# MB-7SEGMENT-74HC595.net
KiCad netlist of a schematic drawn in EAGLE
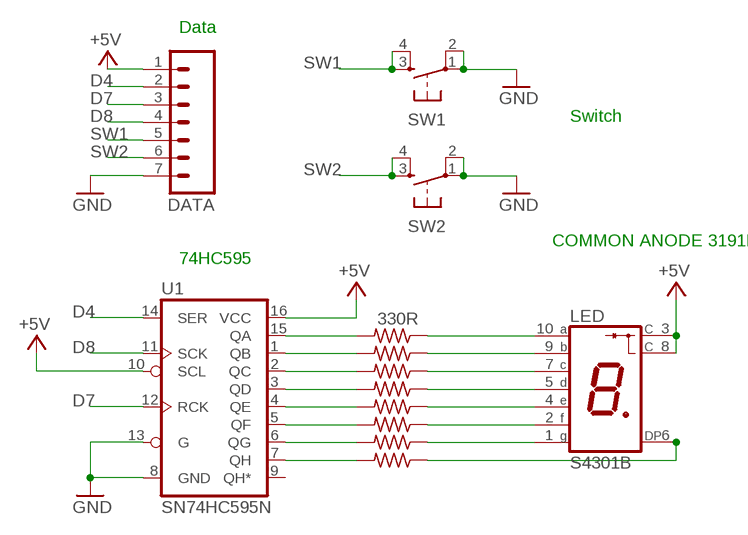
[diagram p0: schematic, sheet 1]

(export (version "E")
  (design (tool "Eeschema 10.0.6"))
  (components
    (comp (ref "DATA")
      (value "M07")
      (footprint "eagle-import:1X07")
      (libsource (lib "eagle-import") (part "M07"))
    )
    (comp (ref "LED")
      (value "S4301B")
      (footprint "eagle-import:S4301B")
      (libsource (lib "eagle-import") (part "S4301B"))
    )
    (comp (ref "R1")
      (value "330R")
      (footprint "eagle-import:0204_5")
      (libsource (lib "eagle-import") (part "R-US_0204/5"))
    )
    (comp (ref "R3")
      (value "330R")
      (footprint "eagle-import:0204_5")
      (libsource (lib "eagle-import") (part "R-US_0204/5"))
    )
    (comp (ref "R4")
      (value "330R")
      (footprint "eagle-import:0204_5")
      (libsource (lib "eagle-import") (part "R-US_0204/5"))
    )
    (comp (ref "R5")
      (value "330R")
      (footprint "eagle-import:0204_5")
      (libsource (lib "eagle-import") (part "R-US_0204/5"))
    )
    (comp (ref "R6")
      (value "330R")
      (footprint "eagle-import:0204_5")
      (libsource (lib "eagle-import") (part "R-US_0204/5"))
    )
    (comp (ref "R7")
      (value "330R")
      (footprint "eagle-import:0204_5")
      (libsource (lib "eagle-import") (part "R-US_0204/5"))
    )
    (comp (ref "R8")
      (value "330R")
      (footprint "eagle-import:0204_5")
      (libsource (lib "eagle-import") (part "R-US_0204/5"))
    )
    (comp (ref "R9")
      (value "330R")
      (footprint "eagle-import:0204_5")
      (libsource (lib "eagle-import") (part "R-US_0204/5"))
    )
    (comp (ref "SW1")
      (value "DTS-6")
      (footprint "eagle-import:DTS-6")
      (libsource (lib "eagle-import") (part "DTS-6"))
    )
    (comp (ref "SW2")
      (value "DTS-6")
      (footprint "eagle-import:DTS-6")
      (libsource (lib "eagle-import") (part "DTS-6"))
    )
    (comp (ref "U1")
      (value "SN74HC595N")
      (footprint "eagle-import:DIP16")
      (libsource (lib "eagle-import") (part "74595NHC"))
    )
  )
  (nets
    (net (code "1") (name "+5V") (class "Default")
      (node (ref "DATA") (pin "1") (pinfunction "1_1") (pintype "passive"))
      (node (ref "LED") (pin "3") (pinfunction "C_3") (pintype "passive"))
      (node (ref "LED") (pin "8") (pinfunction "C_8") (pintype "passive"))
      (node (ref "U1") (pin "10") (pinfunction "SCL_10") (pintype "input"))
      (node (ref "U1") (pin "16") (pinfunction "VCC_16") (pintype "power_in"))
    )
    (net (code "2") (name "/D4") (class "Default")
      (node (ref "DATA") (pin "2") (pinfunction "2_2") (pintype "passive"))
      (node (ref "U1") (pin "14") (pinfunction "SER_14") (pintype "input"))
    )
    (net (code "3") (name "/D7") (class "Default")
      (node (ref "DATA") (pin "3") (pinfunction "3_3") (pintype "passive"))
      (node (ref "U1") (pin "12") (pinfunction "RCK_12") (pintype "input"))
    )
    (net (code "4") (name "/D8") (class "Default")
      (node (ref "DATA") (pin "4") (pinfunction "4_4") (pintype "passive"))
      (node (ref "U1") (pin "11") (pinfunction "SCK_11") (pintype "input"))
    )
    (net (code "5") (name "/SW1") (class "Default")
      (node (ref "DATA") (pin "5") (pinfunction "5_5") (pintype "passive"))
      (node (ref "SW1") (pin "3") (pinfunction "3_3") (pintype "passive"))
      (node (ref "SW1") (pin "4") (pinfunction "4_4") (pintype "passive"))
    )
    (net (code "6") (name "/SW2") (class "Default")
      (node (ref "DATA") (pin "6") (pinfunction "6_6") (pintype "passive"))
      (node (ref "SW2") (pin "3") (pinfunction "3_3") (pintype "passive"))
      (node (ref "SW2") (pin "4") (pinfunction "4_4") (pintype "passive"))
    )
    (net (code "7") (name "GND") (class "Default")
      (node (ref "DATA") (pin "7") (pinfunction "7_7") (pintype "passive"))
      (node (ref "SW1") (pin "1") (pinfunction "1_1") (pintype "passive"))
      (node (ref "SW1") (pin "2") (pinfunction "2_2") (pintype "passive"))
      (node (ref "SW2") (pin "1") (pinfunction "1_1") (pintype "passive"))
      (node (ref "SW2") (pin "2") (pinfunction "2_2") (pintype "passive"))
      (node (ref "U1") (pin "13") (pinfunction "G_13") (pintype "input"))
      (node (ref "U1") (pin "8") (pinfunction "GND_8") (pintype "power_in"))
    )
    (net (code "8") (name "Net-(LED-A)") (class "Default")
      (node (ref "LED") (pin "10") (pinfunction "A_10") (pintype "passive"))
      (node (ref "R1") (pin "1") (pinfunction "1_1") (pintype "passive"))
    )
    (net (code "9") (name "Net-(LED-B)") (class "Default")
      (node (ref "LED") (pin "9") (pinfunction "B_9") (pintype "passive"))
      (node (ref "R3") (pin "1") (pinfunction "1_1") (pintype "passive"))
    )
    (net (code "10") (name "Net-(LED-C-Pad7)") (class "Default")
      (node (ref "LED") (pin "7") (pinfunction "C_7") (pintype "passive"))
      (node (ref "R4") (pin "1") (pinfunction "1_1") (pintype "passive"))
    )
    (net (code "11") (name "Net-(LED-D)") (class "Default")
      (node (ref "LED") (pin "5") (pinfunction "D_5") (pintype "passive"))
      (node (ref "R5") (pin "1") (pinfunction "1_1") (pintype "passive"))
    )
    (net (code "12") (name "Net-(LED-DP)") (class "Default")
      (node (ref "LED") (pin "6") (pinfunction "DP_6") (pintype "passive"))
      (node (ref "R9") (pin "1") (pinfunction "1_1") (pintype "passive"))
    )
    (net (code "13") (name "Net-(LED-E)") (class "Default")
      (node (ref "LED") (pin "4") (pinfunction "E_4") (pintype "passive"))
      (node (ref "R6") (pin "1") (pinfunction "1_1") (pintype "passive"))
    )
    (net (code "14") (name "Net-(LED-F)") (class "Default")
      (node (ref "LED") (pin "2") (pinfunction "F_2") (pintype "passive"))
      (node (ref "R7") (pin "1") (pinfunction "1_1") (pintype "passive"))
    )
    (net (code "15") (name "Net-(LED-G)") (class "Default")
      (node (ref "LED") (pin "1") (pinfunction "G_1") (pintype "passive"))
      (node (ref "R8") (pin "1") (pinfunction "1_1") (pintype "passive"))
    )
    (net (code "16") (name "Net-(U1-QA)") (class "Default")
      (node (ref "R1") (pin "2") (pinfunction "2_2") (pintype "passive"))
      (node (ref "U1") (pin "15") (pinfunction "QA_15") (pintype "tri_state"))
    )
    (net (code "17") (name "Net-(U1-QB)") (class "Default")
      (node (ref "R3") (pin "2") (pinfunction "2_2") (pintype "passive"))
      (node (ref "U1") (pin "1") (pinfunction "QB_1") (pintype "tri_state"))
    )
    (net (code "18") (name "Net-(U1-QC)") (class "Default")
      (node (ref "R4") (pin "2") (pinfunction "2_2") (pintype "passive"))
      (node (ref "U1") (pin "2") (pinfunction "QC_2") (pintype "tri_state"))
    )
    (net (code "19") (name "Net-(U1-QD)") (class "Default")
      (node (ref "R5") (pin "2") (pinfunction "2_2") (pintype "passive"))
      (node (ref "U1") (pin "3") (pinfunction "QD_3") (pintype "tri_state"))
    )
    (net (code "20") (name "Net-(U1-QE)") (class "Default")
      (node (ref "R6") (pin "2") (pinfunction "2_2") (pintype "passive"))
      (node (ref "U1") (pin "4") (pinfunction "QE_4") (pintype "tri_state"))
    )
    (net (code "21") (name "Net-(U1-QF)") (class "Default")
      (node (ref "R7") (pin "2") (pinfunction "2_2") (pintype "passive"))
      (node (ref "U1") (pin "5") (pinfunction "QF_5") (pintype "tri_state"))
    )
    (net (code "22") (name "Net-(U1-QG)") (class "Default")
      (node (ref "R8") (pin "2") (pinfunction "2_2") (pintype "passive"))
      (node (ref "U1") (pin "6") (pinfunction "QG_6") (pintype "tri_state"))
    )
    (net (code "23") (name "Net-(U1-QH)") (class "Default")
      (node (ref "R9") (pin "2") (pinfunction "2_2") (pintype "passive"))
      (node (ref "U1") (pin "7") (pinfunction "QH_7") (pintype "tri_state"))
    )
    (net (code "24") (name "unconnected-(U1-QH*-Pad9)") (class "Default")
      (node (ref "U1") (pin "9") (pinfunction "QH*_9") (pintype "tri_state"))
    )
  )
)
